# LMC.net
KiCad netlist of a schematic drawn in Altium Designer
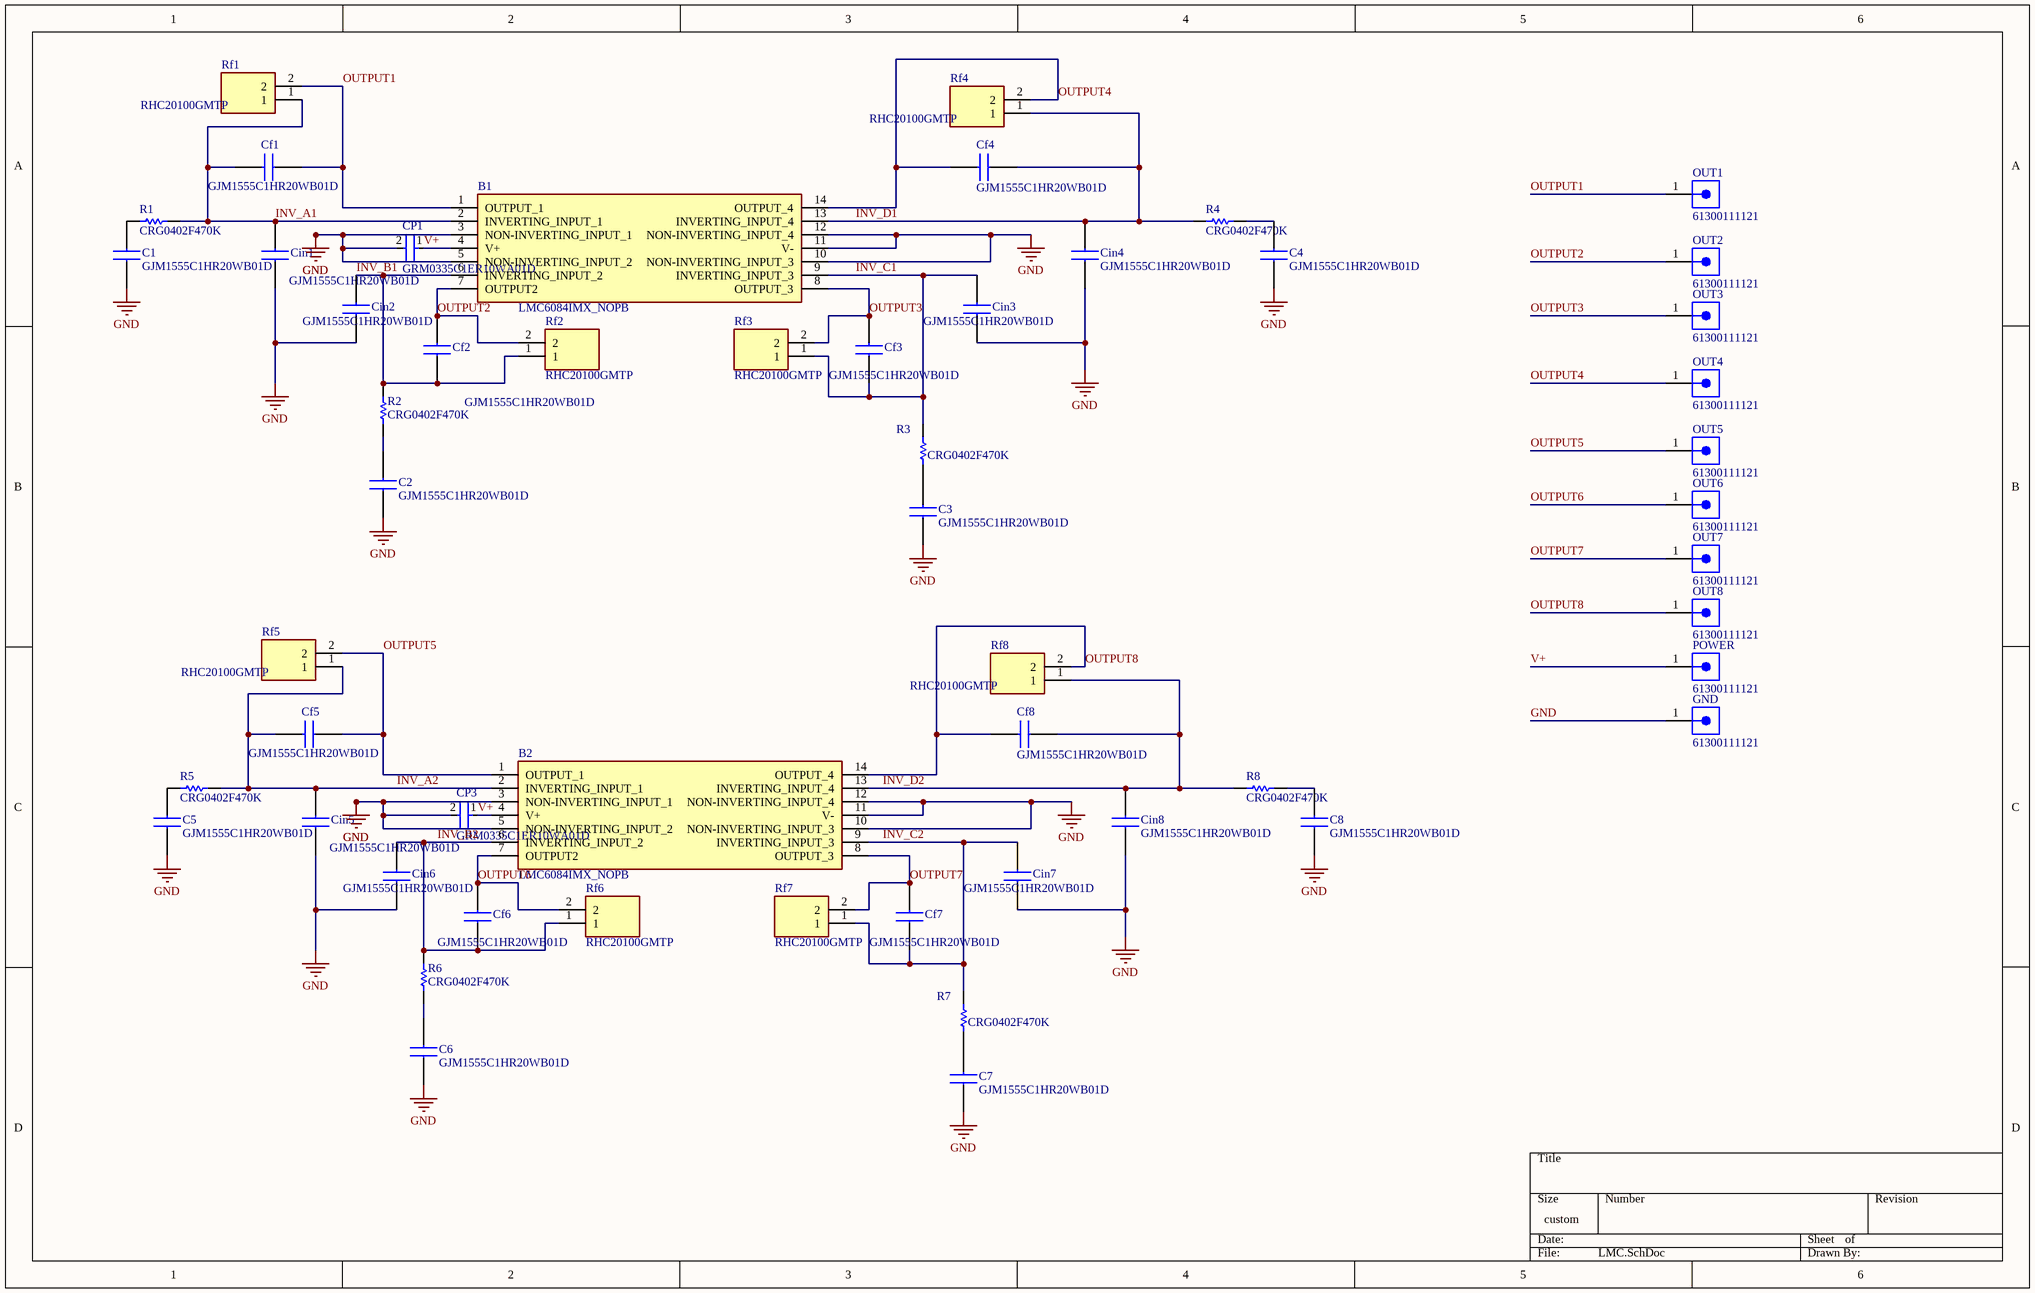
[diagram p0: LMC.SchDoc]

(export (version "E")
  (design (tool "Eeschema 10.0.6"))
  (components
    (comp (ref "B1")
      (value "LMC6084IMX_NOPB")
      (footprint "SOIC127P600X175-14N:SOIC127P600X175-14N")
      (description "Precision CMOS Quad Operational Amplifier")
      (fields
        (field (name "MANUFACTURER_PART_NUMBER") "LMC6084IMX/NOPB")
        (field (name "MOUSER PART NUMBER") "926-LMC6084IMX/NOPB")
      )
      (libsource (lib "LMC6084IMX_NOPB") (part "LMC6084IMX_NOPB"))
    )
    (comp (ref "B2")
      (value "LMC6084IMX_NOPB")
      (footprint "SOIC127P600X175-14N:SOIC127P600X175-14N")
      (description "Precision CMOS Quad Operational Amplifier")
      (fields
        (field (name "MANUFACTURER_PART_NUMBER") "LMC6084IMX/NOPB")
        (field (name "MOUSER PART NUMBER") "926-LMC6084IMX/NOPB")
      )
      (libsource (lib "LMC6084IMX_NOPB") (part "LMC6084IMX_NOPB"))
    )
    (comp (ref "C1")
      (value "GJM1555C1HR20WB01D")
      (footprint "CAPC1005X55N:CAPC1005X55N")
      (description "Capacitor GJM15_0.10 L=1.0mm W=0.5mm T=0.5mm")
      (fields (field (name "MOUSER PART NUMBER") "81-GJM1555C1HR20WB01"))
      (libsource (lib "GJM1555C1HR20WB01D") (part "GJM1555C1HR20WB01D"))
    )
    (comp (ref "C2")
      (value "GJM1555C1HR20WB01D")
      (footprint "CAPC1005X55N:CAPC1005X55N")
      (description "Capacitor GJM15_0.10 L=1.0mm W=0.5mm T=0.5mm")
      (fields (field (name "MOUSER PART NUMBER") "81-GJM1555C1HR20WB01"))
      (libsource (lib "GJM1555C1HR20WB01D") (part "GJM1555C1HR20WB01D"))
    )
    (comp (ref "C3")
      (value "GJM1555C1HR20WB01D")
      (footprint "CAPC1005X55N:CAPC1005X55N")
      (description "Capacitor GJM15_0.10 L=1.0mm W=0.5mm T=0.5mm")
      (fields (field (name "MOUSER PART NUMBER") "81-GJM1555C1HR20WB01"))
      (libsource (lib "GJM1555C1HR20WB01D") (part "GJM1555C1HR20WB01D"))
    )
    (comp (ref "C4")
      (value "GJM1555C1HR20WB01D")
      (footprint "CAPC1005X55N:CAPC1005X55N")
      (description "Capacitor GJM15_0.10 L=1.0mm W=0.5mm T=0.5mm")
      (fields (field (name "MOUSER PART NUMBER") "81-GJM1555C1HR20WB01"))
      (libsource (lib "GJM1555C1HR20WB01D") (part "GJM1555C1HR20WB01D"))
    )
    (comp (ref "C5")
      (value "GJM1555C1HR20WB01D")
      (footprint "CAPC1005X55N:CAPC1005X55N")
      (description "Capacitor GJM15_0.10 L=1.0mm W=0.5mm T=0.5mm")
      (fields (field (name "MOUSER PART NUMBER") "81-GJM1555C1HR20WB01"))
      (libsource (lib "GJM1555C1HR20WB01D") (part "GJM1555C1HR20WB01D"))
    )
    (comp (ref "C6")
      (value "GJM1555C1HR20WB01D")
      (footprint "CAPC1005X55N:CAPC1005X55N")
      (description "Capacitor GJM15_0.10 L=1.0mm W=0.5mm T=0.5mm")
      (fields (field (name "MOUSER PART NUMBER") "81-GJM1555C1HR20WB01"))
      (libsource (lib "GJM1555C1HR20WB01D") (part "GJM1555C1HR20WB01D"))
    )
    (comp (ref "C7")
      (value "GJM1555C1HR20WB01D")
      (footprint "CAPC1005X55N:CAPC1005X55N")
      (description "Capacitor GJM15_0.10 L=1.0mm W=0.5mm T=0.5mm")
      (fields (field (name "MOUSER PART NUMBER") "81-GJM1555C1HR20WB01"))
      (libsource (lib "GJM1555C1HR20WB01D") (part "GJM1555C1HR20WB01D"))
    )
    (comp (ref "C8")
      (value "GJM1555C1HR20WB01D")
      (footprint "CAPC1005X55N:CAPC1005X55N")
      (description "Capacitor GJM15_0.10 L=1.0mm W=0.5mm T=0.5mm")
      (fields (field (name "MOUSER PART NUMBER") "81-GJM1555C1HR20WB01"))
      (libsource (lib "GJM1555C1HR20WB01D") (part "GJM1555C1HR20WB01D"))
    )
    (comp (ref "Cf1")
      (value "GJM1555C1HR20WB01D")
      (footprint "CAPC1005X55N:CAPC1005X55N")
      (description "Capacitor GJM15_0.10 L=1.0mm W=0.5mm T=0.5mm")
      (fields (field (name "MOUSER PART NUMBER") "81-GJM1555C1HR20WB01"))
      (libsource (lib "GJM1555C1HR20WB01D") (part "GJM1555C1HR20WB01D"))
    )
    (comp (ref "Cf2")
      (value "GJM1555C1HR20WB01D")
      (footprint "CAPC1005X55N:CAPC1005X55N")
      (description "Capacitor GJM15_0.10 L=1.0mm W=0.5mm T=0.5mm")
      (fields (field (name "MOUSER PART NUMBER") "81-GJM1555C1HR20WB01"))
      (libsource (lib "GJM1555C1HR20WB01D") (part "GJM1555C1HR20WB01D"))
    )
    (comp (ref "Cf3")
      (value "GJM1555C1HR20WB01D")
      (footprint "CAPC1005X55N:CAPC1005X55N")
      (description "Capacitor GJM15_0.10 L=1.0mm W=0.5mm T=0.5mm")
      (fields (field (name "MOUSER PART NUMBER") "81-GJM1555C1HR20WB01"))
      (libsource (lib "GJM1555C1HR20WB01D") (part "GJM1555C1HR20WB01D"))
    )
    (comp (ref "Cf4")
      (value "GJM1555C1HR20WB01D")
      (footprint "CAPC1005X55N:CAPC1005X55N")
      (description "Capacitor GJM15_0.10 L=1.0mm W=0.5mm T=0.5mm")
      (fields (field (name "MOUSER PART NUMBER") "81-GJM1555C1HR20WB01"))
      (libsource (lib "GJM1555C1HR20WB01D") (part "GJM1555C1HR20WB01D"))
    )
    (comp (ref "Cf5")
      (value "GJM1555C1HR20WB01D")
      (footprint "CAPC1005X55N:CAPC1005X55N")
      (description "Capacitor GJM15_0.10 L=1.0mm W=0.5mm T=0.5mm")
      (fields (field (name "MOUSER PART NUMBER") "81-GJM1555C1HR20WB01"))
      (libsource (lib "GJM1555C1HR20WB01D") (part "GJM1555C1HR20WB01D"))
    )
    (comp (ref "Cf6")
      (value "GJM1555C1HR20WB01D")
      (footprint "CAPC1005X55N:CAPC1005X55N")
      (description "Capacitor GJM15_0.10 L=1.0mm W=0.5mm T=0.5mm")
      (fields (field (name "MOUSER PART NUMBER") "81-GJM1555C1HR20WB01"))
      (libsource (lib "GJM1555C1HR20WB01D") (part "GJM1555C1HR20WB01D"))
    )
    (comp (ref "Cf7")
      (value "GJM1555C1HR20WB01D")
      (footprint "CAPC1005X55N:CAPC1005X55N")
      (description "Capacitor GJM15_0.10 L=1.0mm W=0.5mm T=0.5mm")
      (fields (field (name "MOUSER PART NUMBER") "81-GJM1555C1HR20WB01"))
      (libsource (lib "GJM1555C1HR20WB01D") (part "GJM1555C1HR20WB01D"))
    )
    (comp (ref "Cf8")
      (value "GJM1555C1HR20WB01D")
      (footprint "CAPC1005X55N:CAPC1005X55N")
      (description "Capacitor GJM15_0.10 L=1.0mm W=0.5mm T=0.5mm")
      (fields (field (name "MOUSER PART NUMBER") "81-GJM1555C1HR20WB01"))
      (libsource (lib "GJM1555C1HR20WB01D") (part "GJM1555C1HR20WB01D"))
    )
    (comp (ref "Cin1")
      (value "GJM1555C1HR20WB01D")
      (footprint "CAPC1005X55N:CAPC1005X55N")
      (description "Capacitor GJM15_0.10 L=1.0mm W=0.5mm T=0.5mm")
      (fields (field (name "MOUSER PART NUMBER") "81-GJM1555C1HR20WB01"))
      (libsource (lib "GJM1555C1HR20WB01D") (part "GJM1555C1HR20WB01D"))
    )
    (comp (ref "Cin2")
      (value "GJM1555C1HR20WB01D")
      (footprint "CAPC1005X55N:CAPC1005X55N")
      (description "Capacitor GJM15_0.10 L=1.0mm W=0.5mm T=0.5mm")
      (fields (field (name "MOUSER PART NUMBER") "81-GJM1555C1HR20WB01"))
      (libsource (lib "GJM1555C1HR20WB01D") (part "GJM1555C1HR20WB01D"))
    )
    (comp (ref "Cin3")
      (value "GJM1555C1HR20WB01D")
      (footprint "CAPC1005X55N:CAPC1005X55N")
      (description "Capacitor GJM15_0.10 L=1.0mm W=0.5mm T=0.5mm")
      (fields (field (name "MOUSER PART NUMBER") "81-GJM1555C1HR20WB01"))
      (libsource (lib "GJM1555C1HR20WB01D") (part "GJM1555C1HR20WB01D"))
    )
    (comp (ref "Cin4")
      (value "GJM1555C1HR20WB01D")
      (footprint "CAPC1005X55N:CAPC1005X55N")
      (description "Capacitor GJM15_0.10 L=1.0mm W=0.5mm T=0.5mm")
      (fields (field (name "MOUSER PART NUMBER") "81-GJM1555C1HR20WB01"))
      (libsource (lib "GJM1555C1HR20WB01D") (part "GJM1555C1HR20WB01D"))
    )
    (comp (ref "Cin5")
      (value "GJM1555C1HR20WB01D")
      (footprint "CAPC1005X55N:CAPC1005X55N")
      (description "Capacitor GJM15_0.10 L=1.0mm W=0.5mm T=0.5mm")
      (fields (field (name "MOUSER PART NUMBER") "81-GJM1555C1HR20WB01"))
      (libsource (lib "GJM1555C1HR20WB01D") (part "GJM1555C1HR20WB01D"))
    )
    (comp (ref "Cin6")
      (value "GJM1555C1HR20WB01D")
      (footprint "CAPC1005X55N:CAPC1005X55N")
      (description "Capacitor GJM15_0.10 L=1.0mm W=0.5mm T=0.5mm")
      (fields (field (name "MOUSER PART NUMBER") "81-GJM1555C1HR20WB01"))
      (libsource (lib "GJM1555C1HR20WB01D") (part "GJM1555C1HR20WB01D"))
    )
    (comp (ref "Cin7")
      (value "GJM1555C1HR20WB01D")
      (footprint "CAPC1005X55N:CAPC1005X55N")
      (description "Capacitor GJM15_0.10 L=1.0mm W=0.5mm T=0.5mm")
      (fields (field (name "MOUSER PART NUMBER") "81-GJM1555C1HR20WB01"))
      (libsource (lib "GJM1555C1HR20WB01D") (part "GJM1555C1HR20WB01D"))
    )
    (comp (ref "Cin8")
      (value "GJM1555C1HR20WB01D")
      (footprint "CAPC1005X55N:CAPC1005X55N")
      (description "Capacitor GJM15_0.10 L=1.0mm W=0.5mm T=0.5mm")
      (fields (field (name "MOUSER PART NUMBER") "81-GJM1555C1HR20WB01"))
      (libsource (lib "GJM1555C1HR20WB01D") (part "GJM1555C1HR20WB01D"))
    )
    (comp (ref "CP1")
      (value "GRM0335C1ER10WA01D")
      (footprint "FP-GRM033-0_03-IPC_A")
      (description "Chip Multilayer Ceramic Capacitors for General Purpose, 0201, 0.10pF, C0G, 30ppm/°C, 0.05pF, 25V")
      (libsource (lib "Altium Content Vault") (part "b4654b650e69147ec39a6b967a45e02"))
    )
    (comp (ref "CP3")
      (value "GRM0335C1ER10WA01D")
      (footprint "FP-GRM033-0_03-IPC_A")
      (description "Chip Multilayer Ceramic Capacitors for General Purpose, 0201, 0.10pF, C0G, 30ppm/°C, 0.05pF, 25V")
      (libsource (lib "Altium Content Vault") (part "b4654b650e69147ec39a6b967a45e02"))
    )
    (comp (ref "GND")
      (value "61300111121")
      (footprint "61300111121")
      (description "THT Vertical Pin Header WR-PHD, Pitch 2.54 mm, Single Row, 1 pins")
      (libsource (lib "Altium Content Vault") (part "Header_Male_1R_01P"))
    )
    (comp (ref "OUT1")
      (value "61300111121")
      (footprint "61300111121")
      (description "THT Vertical Pin Header WR-PHD, Pitch 2.54 mm, Single Row, 1 pins")
      (libsource (lib "Altium Content Vault") (part "Header_Male_1R_01P"))
    )
    (comp (ref "OUT2")
      (value "61300111121")
      (footprint "61300111121")
      (description "THT Vertical Pin Header WR-PHD, Pitch 2.54 mm, Single Row, 1 pins")
      (libsource (lib "Altium Content Vault") (part "Header_Male_1R_01P"))
    )
    (comp (ref "OUT3")
      (value "61300111121")
      (footprint "61300111121")
      (description "THT Vertical Pin Header WR-PHD, Pitch 2.54 mm, Single Row, 1 pins")
      (libsource (lib "Altium Content Vault") (part "Header_Male_1R_01P"))
    )
    (comp (ref "OUT4")
      (value "61300111121")
      (footprint "61300111121")
      (description "THT Vertical Pin Header WR-PHD, Pitch 2.54 mm, Single Row, 1 pins")
      (libsource (lib "Altium Content Vault") (part "Header_Male_1R_01P"))
    )
    (comp (ref "OUT5")
      (value "61300111121")
      (footprint "61300111121")
      (description "THT Vertical Pin Header WR-PHD, Pitch 2.54 mm, Single Row, 1 pins")
      (libsource (lib "Altium Content Vault") (part "Header_Male_1R_01P"))
    )
    (comp (ref "OUT6")
      (value "61300111121")
      (footprint "61300111121")
      (description "THT Vertical Pin Header WR-PHD, Pitch 2.54 mm, Single Row, 1 pins")
      (libsource (lib "Altium Content Vault") (part "Header_Male_1R_01P"))
    )
    (comp (ref "OUT7")
      (value "61300111121")
      (footprint "61300111121")
      (description "THT Vertical Pin Header WR-PHD, Pitch 2.54 mm, Single Row, 1 pins")
      (libsource (lib "Altium Content Vault") (part "Header_Male_1R_01P"))
    )
    (comp (ref "OUT8")
      (value "61300111121")
      (footprint "61300111121")
      (description "THT Vertical Pin Header WR-PHD, Pitch 2.54 mm, Single Row, 1 pins")
      (libsource (lib "Altium Content Vault") (part "Header_Male_1R_01P"))
    )
    (comp (ref "POWER")
      (value "61300111121")
      (footprint "61300111121")
      (description "THT Vertical Pin Header WR-PHD, Pitch 2.54 mm, Single Row, 1 pins")
      (libsource (lib "Altium Content Vault") (part "Header_Male_1R_01P"))
    )
    (comp (ref "R1")
      (value "CRG0402F470K")
      (footprint "RESC1005X40X25LL10T10")
      (fields (field (name "MANUFACTURER") "TE Connectivity / AMP"))
      (libsource (lib "Altium Content Vault") (part "RES"))
    )
    (comp (ref "R2")
      (value "CRG0402F470K")
      (footprint "RESC1005X40X25LL10T10")
      (fields (field (name "MANUFACTURER") "TE Connectivity / AMP"))
      (libsource (lib "Altium Content Vault") (part "RES"))
    )
    (comp (ref "R3")
      (value "CRG0402F470K")
      (footprint "RESC1005X40X25LL10T10")
      (fields (field (name "MANUFACTURER") "TE Connectivity / AMP"))
      (libsource (lib "Altium Content Vault") (part "RES"))
    )
    (comp (ref "R4")
      (value "CRG0402F470K")
      (footprint "RESC1005X40X25LL10T10")
      (fields (field (name "MANUFACTURER") "TE Connectivity / AMP"))
      (libsource (lib "Altium Content Vault") (part "RES"))
    )
    (comp (ref "R5")
      (value "CRG0402F470K")
      (footprint "RESC1005X40X25LL10T10")
      (fields (field (name "MANUFACTURER") "TE Connectivity / AMP"))
      (libsource (lib "Altium Content Vault") (part "RES"))
    )
    (comp (ref "R6")
      (value "CRG0402F470K")
      (footprint "RESC1005X40X25LL10T10")
      (fields (field (name "MANUFACTURER") "TE Connectivity / AMP"))
      (libsource (lib "Altium Content Vault") (part "RES"))
    )
    (comp (ref "R7")
      (value "CRG0402F470K")
      (footprint "RESC1005X40X25LL10T10")
      (fields (field (name "MANUFACTURER") "TE Connectivity / AMP"))
      (libsource (lib "Altium Content Vault") (part "RES"))
    )
    (comp (ref "R8")
      (value "CRG0402F470K")
      (footprint "RESC1005X40X25LL10T10")
      (fields (field (name "MANUFACTURER") "TE Connectivity / AMP"))
      (libsource (lib "Altium Content Vault") (part "RES"))
    )
    (comp (ref "Rf1")
      (value "RHC20100GMTP")
      (footprint "RESC2012X65N:RESC2012X65N")
      (description "Thick Film Resistors - SMD 0805 100G 20%")
      (fields (field (name "MOUSER PART NUMBER") "791-RHC20100GMTP"))
      (libsource (lib "RHC20100GMTP") (part "RHC20100GMTP"))
    )
    (comp (ref "Rf2")
      (value "RHC20100GMTP")
      (footprint "RESC2012X65N:RESC2012X65N")
      (description "Thick Film Resistors - SMD 0805 100G 20%")
      (fields (field (name "MOUSER PART NUMBER") "791-RHC20100GMTP"))
      (libsource (lib "") (part "RHC20100GMTP_1"))
    )
    (comp (ref "Rf3")
      (value "RHC20100GMTP")
      (footprint "RESC2012X65N:RESC2012X65N")
      (description "Thick Film Resistors - SMD 0805 100G 20%")
      (fields (field (name "MOUSER PART NUMBER") "791-RHC20100GMTP"))
      (libsource (lib "RHC20100GMTP") (part "RHC20100GMTP"))
    )
    (comp (ref "Rf4")
      (value "RHC20100GMTP")
      (footprint "RESC2012X65N:RESC2012X65N")
      (description "Thick Film Resistors - SMD 0805 100G 20%")
      (fields (field (name "MOUSER PART NUMBER") "791-RHC20100GMTP"))
      (libsource (lib "RHC20100GMTP") (part "RHC20100GMTP"))
    )
    (comp (ref "Rf5")
      (value "RHC20100GMTP")
      (footprint "RESC2012X65N:RESC2012X65N")
      (description "Thick Film Resistors - SMD 0805 100G 20%")
      (fields (field (name "MOUSER PART NUMBER") "791-RHC20100GMTP"))
      (libsource (lib "RHC20100GMTP") (part "RHC20100GMTP"))
    )
    (comp (ref "Rf6")
      (value "RHC20100GMTP")
      (footprint "RESC2012X65N:RESC2012X65N")
      (description "Thick Film Resistors - SMD 0805 100G 20%")
      (fields (field (name "MOUSER PART NUMBER") "791-RHC20100GMTP"))
      (libsource (lib "") (part "RHC20100GMTP_1"))
    )
    (comp (ref "Rf7")
      (value "RHC20100GMTP")
      (footprint "RESC2012X65N:RESC2012X65N")
      (description "Thick Film Resistors - SMD 0805 100G 20%")
      (fields (field (name "MOUSER PART NUMBER") "791-RHC20100GMTP"))
      (libsource (lib "RHC20100GMTP") (part "RHC20100GMTP"))
    )
    (comp (ref "Rf8")
      (value "RHC20100GMTP")
      (footprint "RESC2012X65N:RESC2012X65N")
      (description "Thick Film Resistors - SMD 0805 100G 20%")
      (fields (field (name "MOUSER PART NUMBER") "791-RHC20100GMTP"))
      (libsource (lib "RHC20100GMTP") (part "RHC20100GMTP"))
    )
  )
  (nets
    (net (code "1") (name "/INV_A1") (class "Default")
      (node (ref "B1") (pin "2") (pinfunction "INVERTING_INPUT_1_2") (pintype "passive"))
      (node (ref "Cf1") (pin "2") (pinfunction "2_2") (pintype "passive"))
      (node (ref "Cin1") (pin "2") (pinfunction "2_2") (pintype "passive"))
      (node (ref "R1") (pin "2") (pinfunction "2_2") (pintype "passive"))
      (node (ref "Rf1") (pin "1") (pinfunction "1_1") (pintype "passive"))
    )
    (net (code "2") (name "/INV_A2") (class "Default")
      (node (ref "B2") (pin "2") (pinfunction "INVERTING_INPUT_1_2") (pintype "passive"))
      (node (ref "Cf5") (pin "2") (pinfunction "2_2") (pintype "passive"))
      (node (ref "Cin5") (pin "2") (pinfunction "2_2") (pintype "passive"))
      (node (ref "R5") (pin "2") (pinfunction "2_2") (pintype "passive"))
      (node (ref "Rf5") (pin "1") (pinfunction "1_1") (pintype "passive"))
    )
    (net (code "3") (name "/INV_B1") (class "Default")
      (node (ref "B1") (pin "6") (pinfunction "INVERTING_INPUT_2_6") (pintype "passive"))
      (node (ref "Cf2") (pin "2") (pinfunction "2_2") (pintype "passive"))
      (node (ref "Cin2") (pin "2") (pinfunction "2_2") (pintype "passive"))
      (node (ref "R2") (pin "2") (pinfunction "2_2") (pintype "passive"))
      (node (ref "Rf2") (pin "1") (pinfunction "1_1") (pintype "passive"))
    )
    (net (code "4") (name "/INV_B2") (class "Default")
      (node (ref "B2") (pin "6") (pinfunction "INVERTING_INPUT_2_6") (pintype "passive"))
      (node (ref "Cf6") (pin "2") (pinfunction "2_2") (pintype "passive"))
      (node (ref "Cin6") (pin "2") (pinfunction "2_2") (pintype "passive"))
      (node (ref "R6") (pin "2") (pinfunction "2_2") (pintype "passive"))
      (node (ref "Rf6") (pin "1") (pinfunction "1_1") (pintype "passive"))
    )
    (net (code "5") (name "/INV_C1") (class "Default")
      (node (ref "B1") (pin "9") (pinfunction "INVERTING_INPUT_3_9") (pintype "passive"))
      (node (ref "Cf3") (pin "2") (pinfunction "2_2") (pintype "passive"))
      (node (ref "Cin3") (pin "2") (pinfunction "2_2") (pintype "passive"))
      (node (ref "R3") (pin "2") (pinfunction "2_2") (pintype "passive"))
      (node (ref "Rf3") (pin "1") (pinfunction "1_1") (pintype "passive"))
    )
    (net (code "6") (name "/INV_C2") (class "Default")
      (node (ref "B2") (pin "9") (pinfunction "INVERTING_INPUT_3_9") (pintype "passive"))
      (node (ref "Cf7") (pin "2") (pinfunction "2_2") (pintype "passive"))
      (node (ref "Cin7") (pin "2") (pinfunction "2_2") (pintype "passive"))
      (node (ref "R7") (pin "2") (pinfunction "2_2") (pintype "passive"))
      (node (ref "Rf7") (pin "1") (pinfunction "1_1") (pintype "passive"))
    )
    (net (code "7") (name "/INV_D1") (class "Default")
      (node (ref "B1") (pin "13") (pinfunction "INVERTING_INPUT_4_13") (pintype "passive"))
      (node (ref "Cf4") (pin "2") (pinfunction "2_2") (pintype "passive"))
      (node (ref "Cin4") (pin "2") (pinfunction "2_2") (pintype "passive"))
      (node (ref "R4") (pin "1") (pinfunction "1_1") (pintype "passive"))
      (node (ref "Rf4") (pin "1") (pinfunction "1_1") (pintype "passive"))
    )
    (net (code "8") (name "/INV_D2") (class "Default")
      (node (ref "B2") (pin "13") (pinfunction "INVERTING_INPUT_4_13") (pintype "passive"))
      (node (ref "Cf8") (pin "2") (pinfunction "2_2") (pintype "passive"))
      (node (ref "Cin8") (pin "2") (pinfunction "2_2") (pintype "passive"))
      (node (ref "R8") (pin "1") (pinfunction "1_1") (pintype "passive"))
      (node (ref "Rf8") (pin "1") (pinfunction "1_1") (pintype "passive"))
    )
    (net (code "9") (name "/OUTPUT1") (class "Default")
      (node (ref "B1") (pin "1") (pinfunction "OUTPUT_1_1") (pintype "passive"))
      (node (ref "Cf1") (pin "1") (pinfunction "1_1") (pintype "passive"))
      (node (ref "OUT1") (pin "1") (pinfunction "1_1") (pintype "passive"))
      (node (ref "Rf1") (pin "2") (pinfunction "2_2") (pintype "passive"))
    )
    (net (code "10") (name "/OUTPUT2") (class "Default")
      (node (ref "B1") (pin "7") (pinfunction "OUTPUT2_7") (pintype "passive"))
      (node (ref "Cf2") (pin "1") (pinfunction "1_1") (pintype "passive"))
      (node (ref "OUT2") (pin "1") (pinfunction "1_1") (pintype "passive"))
      (node (ref "Rf2") (pin "2") (pinfunction "2_2") (pintype "passive"))
    )
    (net (code "11") (name "/OUTPUT3") (class "Default")
      (node (ref "B1") (pin "8") (pinfunction "OUTPUT_3_8") (pintype "passive"))
      (node (ref "Cf3") (pin "1") (pinfunction "1_1") (pintype "passive"))
      (node (ref "OUT3") (pin "1") (pinfunction "1_1") (pintype "passive"))
      (node (ref "Rf3") (pin "2") (pinfunction "2_2") (pintype "passive"))
    )
    (net (code "12") (name "/OUTPUT4") (class "Default")
      (node (ref "B1") (pin "14") (pinfunction "OUTPUT_4_14") (pintype "passive"))
      (node (ref "Cf4") (pin "1") (pinfunction "1_1") (pintype "passive"))
      (node (ref "OUT4") (pin "1") (pinfunction "1_1") (pintype "passive"))
      (node (ref "Rf4") (pin "2") (pinfunction "2_2") (pintype "passive"))
    )
    (net (code "13") (name "/OUTPUT5") (class "Default")
      (node (ref "B2") (pin "1") (pinfunction "OUTPUT_1_1") (pintype "passive"))
      (node (ref "Cf5") (pin "1") (pinfunction "1_1") (pintype "passive"))
      (node (ref "OUT5") (pin "1") (pinfunction "1_1") (pintype "passive"))
      (node (ref "Rf5") (pin "2") (pinfunction "2_2") (pintype "passive"))
    )
    (net (code "14") (name "/OUTPUT6") (class "Default")
      (node (ref "B2") (pin "7") (pinfunction "OUTPUT2_7") (pintype "passive"))
      (node (ref "Cf6") (pin "1") (pinfunction "1_1") (pintype "passive"))
      (node (ref "OUT6") (pin "1") (pinfunction "1_1") (pintype "passive"))
      (node (ref "Rf6") (pin "2") (pinfunction "2_2") (pintype "passive"))
    )
    (net (code "15") (name "/OUTPUT7") (class "Default")
      (node (ref "B2") (pin "8") (pinfunction "OUTPUT_3_8") (pintype "passive"))
      (node (ref "Cf7") (pin "1") (pinfunction "1_1") (pintype "passive"))
      (node (ref "OUT7") (pin "1") (pinfunction "1_1") (pintype "passive"))
      (node (ref "Rf7") (pin "2") (pinfunction "2_2") (pintype "passive"))
    )
    (net (code "16") (name "/OUTPUT8") (class "Default")
      (node (ref "B2") (pin "14") (pinfunction "OUTPUT_4_14") (pintype "passive"))
      (node (ref "Cf8") (pin "1") (pinfunction "1_1") (pintype "passive"))
      (node (ref "OUT8") (pin "1") (pinfunction "1_1") (pintype "passive"))
      (node (ref "Rf8") (pin "2") (pinfunction "2_2") (pintype "passive"))
    )
    (net (code "17") (name "/V+") (class "Default")
      (node (ref "B1") (pin "4") (pinfunction "V+_4") (pintype "passive"))
      (node (ref "B2") (pin "4") (pinfunction "V+_4") (pintype "passive"))
      (node (ref "CP1") (pin "1") (pinfunction "1_1") (pintype "passive"))
      (node (ref "CP3") (pin "1") (pinfunction "1_1") (pintype "passive"))
      (node (ref "POWER") (pin "1") (pinfunction "1_1") (pintype "passive"))
    )
    (net (code "18") (name "GND") (class "Default")
      (node (ref "B1") (pin "10") (pinfunction "NON-INVERTING_INPUT_3_10") (pintype "passive"))
      (node (ref "B1") (pin "11") (pinfunction "V-_11") (pintype "passive"))
      (node (ref "B1") (pin "12") (pinfunction "NON-INVERTING_INPUT_4_12") (pintype "passive"))
      (node (ref "B1") (pin "3") (pinfunction "NON-INVERTING_INPUT_1_3") (pintype "passive"))
      (node (ref "B1") (pin "5") (pinfunction "NON-INVERTING_INPUT_2_5") (pintype "passive"))
      (node (ref "B2") (pin "10") (pinfunction "NON-INVERTING_INPUT_3_10") (pintype "passive"))
      (node (ref "B2") (pin "11") (pinfunction "V-_11") (pintype "passive"))
      (node (ref "B2") (pin "12") (pinfunction "NON-INVERTING_INPUT_4_12") (pintype "passive"))
      (node (ref "B2") (pin "3") (pinfunction "NON-INVERTING_INPUT_1_3") (pintype "passive"))
      (node (ref "B2") (pin "5") (pinfunction "NON-INVERTING_INPUT_2_5") (pintype "passive"))
      (node (ref "C1") (pin "1") (pinfunction "1_1") (pintype "passive"))
      (node (ref "C2") (pin "1") (pinfunction "1_1") (pintype "passive"))
      (node (ref "C3") (pin "1") (pinfunction "1_1") (pintype "passive"))
      (node (ref "C4") (pin "1") (pinfunction "1_1") (pintype "passive"))
      (node (ref "C5") (pin "1") (pinfunction "1_1") (pintype "passive"))
      (node (ref "C6") (pin "1") (pinfunction "1_1") (pintype "passive"))
      (node (ref "C7") (pin "1") (pinfunction "1_1") (pintype "passive"))
      (node (ref "C8") (pin "1") (pinfunction "1_1") (pintype "passive"))
      (node (ref "CP1") (pin "2") (pinfunction "2_2") (pintype "passive"))
      (node (ref "CP3") (pin "2") (pinfunction "2_2") (pintype "passive"))
      (node (ref "Cin1") (pin "1") (pinfunction "1_1") (pintype "passive"))
      (node (ref "Cin2") (pin "1") (pinfunction "1_1") (pintype "passive"))
      (node (ref "Cin3") (pin "1") (pinfunction "1_1") (pintype "passive"))
      (node (ref "Cin4") (pin "1") (pinfunction "1_1") (pintype "passive"))
      (node (ref "Cin5") (pin "1") (pinfunction "1_1") (pintype "passive"))
      (node (ref "Cin6") (pin "1") (pinfunction "1_1") (pintype "passive"))
      (node (ref "Cin7") (pin "1") (pinfunction "1_1") (pintype "passive"))
      (node (ref "Cin8") (pin "1") (pinfunction "1_1") (pintype "passive"))
      (node (ref "GND") (pin "1") (pinfunction "1_1") (pintype "passive"))
    )
    (net (code "19") (name "Net-(C1-Pad2)") (class "Default")
      (node (ref "C1") (pin "2") (pinfunction "2_2") (pintype "passive"))
      (node (ref "R1") (pin "1") (pinfunction "1_1") (pintype "passive"))
    )
    (net (code "20") (name "Net-(C2-Pad2)") (class "Default")
      (node (ref "C2") (pin "2") (pinfunction "2_2") (pintype "passive"))
      (node (ref "R2") (pin "1") (pinfunction "1_1") (pintype "passive"))
    )
    (net (code "21") (name "Net-(C3-Pad2)") (class "Default")
      (node (ref "C3") (pin "2") (pinfunction "2_2") (pintype "passive"))
      (node (ref "R3") (pin "1") (pinfunction "1_1") (pintype "passive"))
    )
    (net (code "22") (name "Net-(C4-Pad2)") (class "Default")
      (node (ref "C4") (pin "2") (pinfunction "2_2") (pintype "passive"))
      (node (ref "R4") (pin "2") (pinfunction "2_2") (pintype "passive"))
    )
    (net (code "23") (name "Net-(C5-Pad2)") (class "Default")
      (node (ref "C5") (pin "2") (pinfunction "2_2") (pintype "passive"))
      (node (ref "R5") (pin "1") (pinfunction "1_1") (pintype "passive"))
    )
    (net (code "24") (name "Net-(C6-Pad2)") (class "Default")
      (node (ref "C6") (pin "2") (pinfunction "2_2") (pintype "passive"))
      (node (ref "R6") (pin "1") (pinfunction "1_1") (pintype "passive"))
    )
    (net (code "25") (name "Net-(C7-Pad2)") (class "Default")
      (node (ref "C7") (pin "2") (pinfunction "2_2") (pintype "passive"))
      (node (ref "R7") (pin "1") (pinfunction "1_1") (pintype "passive"))
    )
    (net (code "26") (name "Net-(C8-Pad2)") (class "Default")
      (node (ref "C8") (pin "2") (pinfunction "2_2") (pintype "passive"))
      (node (ref "R8") (pin "2") (pinfunction "2_2") (pintype "passive"))
    )
  )
)
